# rectifier.net
KiCad netlist of a schematic drawn in EAGLE
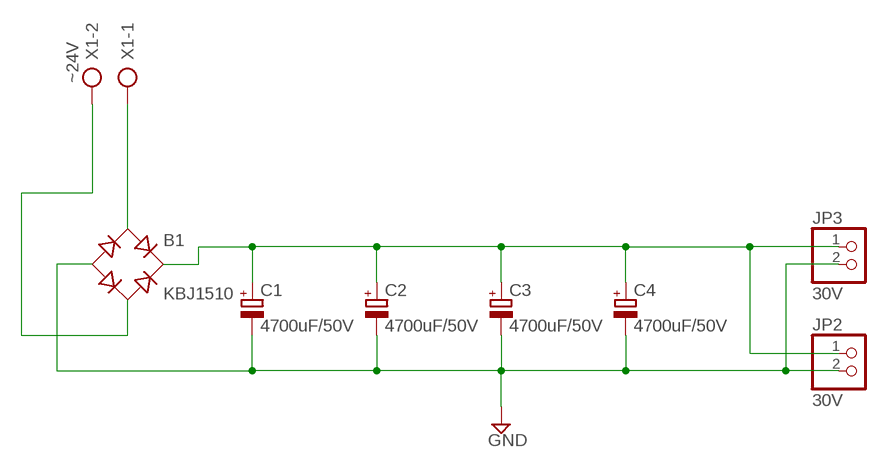
[diagram p0: schematic, sheet 1]

(export (version "E")
  (design (tool "Eeschema 10.0.6"))
  (components
    (comp (ref "B1")
      (value "KBJ1510")
      (footprint "eagle-import:FB32")
      (libsource (lib "eagle-import") (part "RECTIFIER-FB32"))
    )
    (comp (ref "C1")
      (value "4700uF/50V")
      (footprint "eagle-import:EB20D")
      (libsource (lib "eagle-import") (part "CPOL-EUE10-20"))
    )
    (comp (ref "C2")
      (value "4700uF/50V")
      (footprint "eagle-import:EB20D")
      (libsource (lib "eagle-import") (part "CPOL-EUE10-20"))
    )
    (comp (ref "C3")
      (value "4700uF/50V")
      (footprint "eagle-import:EB20D")
      (libsource (lib "eagle-import") (part "CPOL-EUE10-20"))
    )
    (comp (ref "C4")
      (value "4700uF/50V")
      (footprint "eagle-import:EB20D")
      (libsource (lib "eagle-import") (part "CPOL-EUE10-20"))
    )
    (comp (ref "JP2")
      (value "30V")
      (footprint "eagle-import:1X02")
      (libsource (lib "eagle-import") (part "PINHD-1X2"))
    )
    (comp (ref "JP3")
      (value "30V")
      (footprint "eagle-import:1X02")
      (libsource (lib "eagle-import") (part "PINHD-1X2"))
    )
    (comp (ref "X1")
      (value "~24V")
      (footprint "eagle-import:AK500_2")
      (libsource (lib "eagle-import") (part "AK500/2"))
    )
  )
  (nets
    (net (code "1") (name "GND") (class "Default")
      (node (ref "B1") (pin "-") (pinfunction "-_-") (pintype "passive"))
      (node (ref "C1") (pin "-") (pinfunction "-_-") (pintype "passive"))
      (node (ref "C2") (pin "-") (pinfunction "-_-") (pintype "passive"))
      (node (ref "C3") (pin "-") (pinfunction "-_-") (pintype "passive"))
      (node (ref "C4") (pin "-") (pinfunction "-_-") (pintype "passive"))
      (node (ref "JP2") (pin "2") (pinfunction "2_2") (pintype "passive"))
      (node (ref "JP3") (pin "2") (pinfunction "2_2") (pintype "passive"))
    )
    (net (code "2") (name "Net-(B1-Pad+)") (class "Default")
      (node (ref "B1") (pin "+") (pinfunction "+_+") (pintype "passive"))
      (node (ref "C1") (pin "+") (pinfunction "+_+") (pintype "passive"))
      (node (ref "C2") (pin "+") (pinfunction "+_+") (pintype "passive"))
      (node (ref "C3") (pin "+") (pinfunction "+_+") (pintype "passive"))
      (node (ref "C4") (pin "+") (pinfunction "+_+") (pintype "passive"))
      (node (ref "JP2") (pin "1") (pinfunction "1_1") (pintype "passive"))
      (node (ref "JP3") (pin "1") (pinfunction "1_1") (pintype "passive"))
    )
    (net (code "3") (name "Net-(X1A-KL)") (class "Default")
      (node (ref "B1") (pin "AC1") (pinfunction "AC1_AC1") (pintype "passive"))
      (node (ref "X1") (pin "1") (pinfunction "KL_1") (pintype "passive"))
    )
    (net (code "4") (name "Net-(X1B-KL)") (class "Default")
      (node (ref "B1") (pin "AC2") (pinfunction "AC2_AC2") (pintype "passive"))
      (node (ref "X1") (pin "2") (pinfunction "KL_2") (pintype "passive"))
    )
  )
)
